# T1Triak_Diak.net
KiCad netlist of a schematic drawn in EAGLE
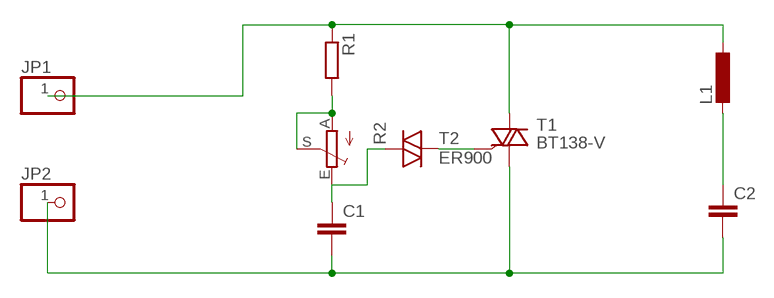
[diagram p0: schematic, sheet 1]

(export (version "E")
  (design (tool "Eeschema 10.0.6"))
  (components
    (comp (ref "C1")
      (value "C-EU225-062X268")
      (footprint "eagle-import:C225-062X268")
      (libsource (lib "eagle-import") (part "C-EU225-062X268"))
    )
    (comp (ref "C2")
      (value "C-EU050-030X075")
      (footprint "eagle-import:C050-030X075")
      (libsource (lib "eagle-import") (part "C-EU050-030X075"))
    )
    (comp (ref "JP1")
      (value "PINHD-1X1")
      (footprint "eagle-import:1X01")
      (libsource (lib "eagle-import") (part "PINHD-1X1"))
    )
    (comp (ref "JP2")
      (value "PINHD-1X1")
      (footprint "eagle-import:1X01")
      (libsource (lib "eagle-import") (part "PINHD-1X1"))
    )
    (comp (ref "L1")
      (value "L-EU0204/5")
      (footprint "eagle-import:0204_5")
      (libsource (lib "eagle-import") (part "L-EU0204/5"))
    )
    (comp (ref "R1")
      (value "R-EU_0207/10")
      (footprint "eagle-import:0207_10")
      (libsource (lib "eagle-import") (part "R-EU_0207/10"))
    )
    (comp (ref "R2")
      (value "TRIM_EU-B64Y")
      (footprint "eagle-import:B64Y")
      (libsource (lib "eagle-import") (part "TRIM_EU-B64Y"))
    )
    (comp (ref "T1")
      (value "BT138-V")
      (footprint "eagle-import:TO220BV")
      (libsource (lib "eagle-import") (part "BT138-V"))
    )
    (comp (ref "T2")
      (value "ER900")
      (footprint "eagle-import:ER900")
      (libsource (lib "eagle-import") (part "ER900"))
    )
  )
  (nets
    (net (code "1") (name "Net-(C1-Pad1)") (class "Default")
      (node (ref "C1") (pin "1") (pinfunction "1_1") (pintype "passive"))
      (node (ref "R2") (pin "E") (pinfunction "E_E") (pintype "passive"))
      (node (ref "T2") (pin "1") (pinfunction "1_1") (pintype "passive"))
    )
    (net (code "2") (name "Net-(C2-Pad1)") (class "Default")
      (node (ref "C2") (pin "1") (pinfunction "1_1") (pintype "passive"))
      (node (ref "L1") (pin "2") (pinfunction "2_2") (pintype "passive"))
    )
    (net (code "3") (name "Net-(R1-Pad2)") (class "Default")
      (node (ref "R1") (pin "2") (pinfunction "2_2") (pintype "passive"))
      (node (ref "R2") (pin "A") (pinfunction "A_A") (pintype "passive"))
      (node (ref "R2") (pin "S") (pinfunction "S_S") (pintype "passive"))
    )
    (net (code "4") (name "Net-(T1-A1)") (class "Default")
      (node (ref "C1") (pin "2") (pinfunction "2_2") (pintype "passive"))
      (node (ref "C2") (pin "2") (pinfunction "2_2") (pintype "passive"))
      (node (ref "JP2") (pin "1") (pinfunction "1_1") (pintype "passive"))
      (node (ref "T1") (pin "T1") (pinfunction "A1_T1") (pintype "passive"))
    )
    (net (code "5") (name "Net-(T1-A2)") (class "Default")
      (node (ref "JP1") (pin "1") (pinfunction "1_1") (pintype "passive"))
      (node (ref "L1") (pin "1") (pinfunction "1_1") (pintype "passive"))
      (node (ref "R1") (pin "1") (pinfunction "1_1") (pintype "passive"))
      (node (ref "T1") (pin "T2") (pinfunction "A2_T2") (pintype "passive"))
    )
    (net (code "6") (name "Net-(T1-PadG)") (class "Default")
      (node (ref "T1") (pin "G") (pinfunction "G_G") (pintype "passive"))
      (node (ref "T2") (pin "2") (pinfunction "2_2") (pintype "passive"))
    )
  )
)
